# batterij_voltage_sensor.net
KiCad netlist of a schematic drawn in Altium Designer
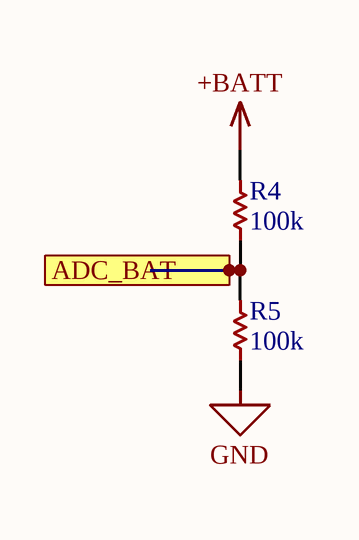
[diagram p0: batterij_voltage_sensor.SchDoc]

(export (version "E")
  (design (tool "Eeschema 10.0.6"))
  (components
    (comp (ref "R4")
      (value "100k")
      (footprint "RESC2013X70X40NL20T20")
      (description "Chip Resistor, 1 KOhm, +/- 1%, 125 mW, -55 to 155 degC, 0805 (2012 Metric), RoHS, Tape and Reel")
      (fields (field (name "TOLERANCE") "1%") (field (name "MANUFACTURER") "Yageo"))
      (libsource (lib "Thermal_Camera") (part "CMP-2100-03671-1"))
    )
    (comp (ref "R5")
      (value "100k")
      (footprint "RESC2013X70X40NL20T20")
      (description "Chip Resistor, 1 KOhm, +/- 1%, 125 mW, -55 to 155 degC, 0805 (2012 Metric), RoHS, Tape and Reel")
      (fields (field (name "TOLERANCE") "1%") (field (name "MANUFACTURER") "Yageo"))
      (libsource (lib "Thermal_Camera") (part "CMP-2100-03671-1"))
    )
  )
  (nets
    (net (code "1") (name "+BATT") (class "Default")
      (node (ref "R4") (pin "2") (pinfunction "2_2") (pintype "passive"))
    )
    (net (code "2") (name "/ADC_BAT") (class "Default")
      (node (ref "R4") (pin "1") (pinfunction "1_1") (pintype "passive"))
      (node (ref "R5") (pin "2") (pinfunction "2_2") (pintype "passive"))
    )
    (net (code "3") (name "GND") (class "Default")
      (node (ref "R5") (pin "1") (pinfunction "1_1") (pintype "passive"))
    )
  )
)
